# design.net
KiCad netlist of a schematic drawn in Altium Designer
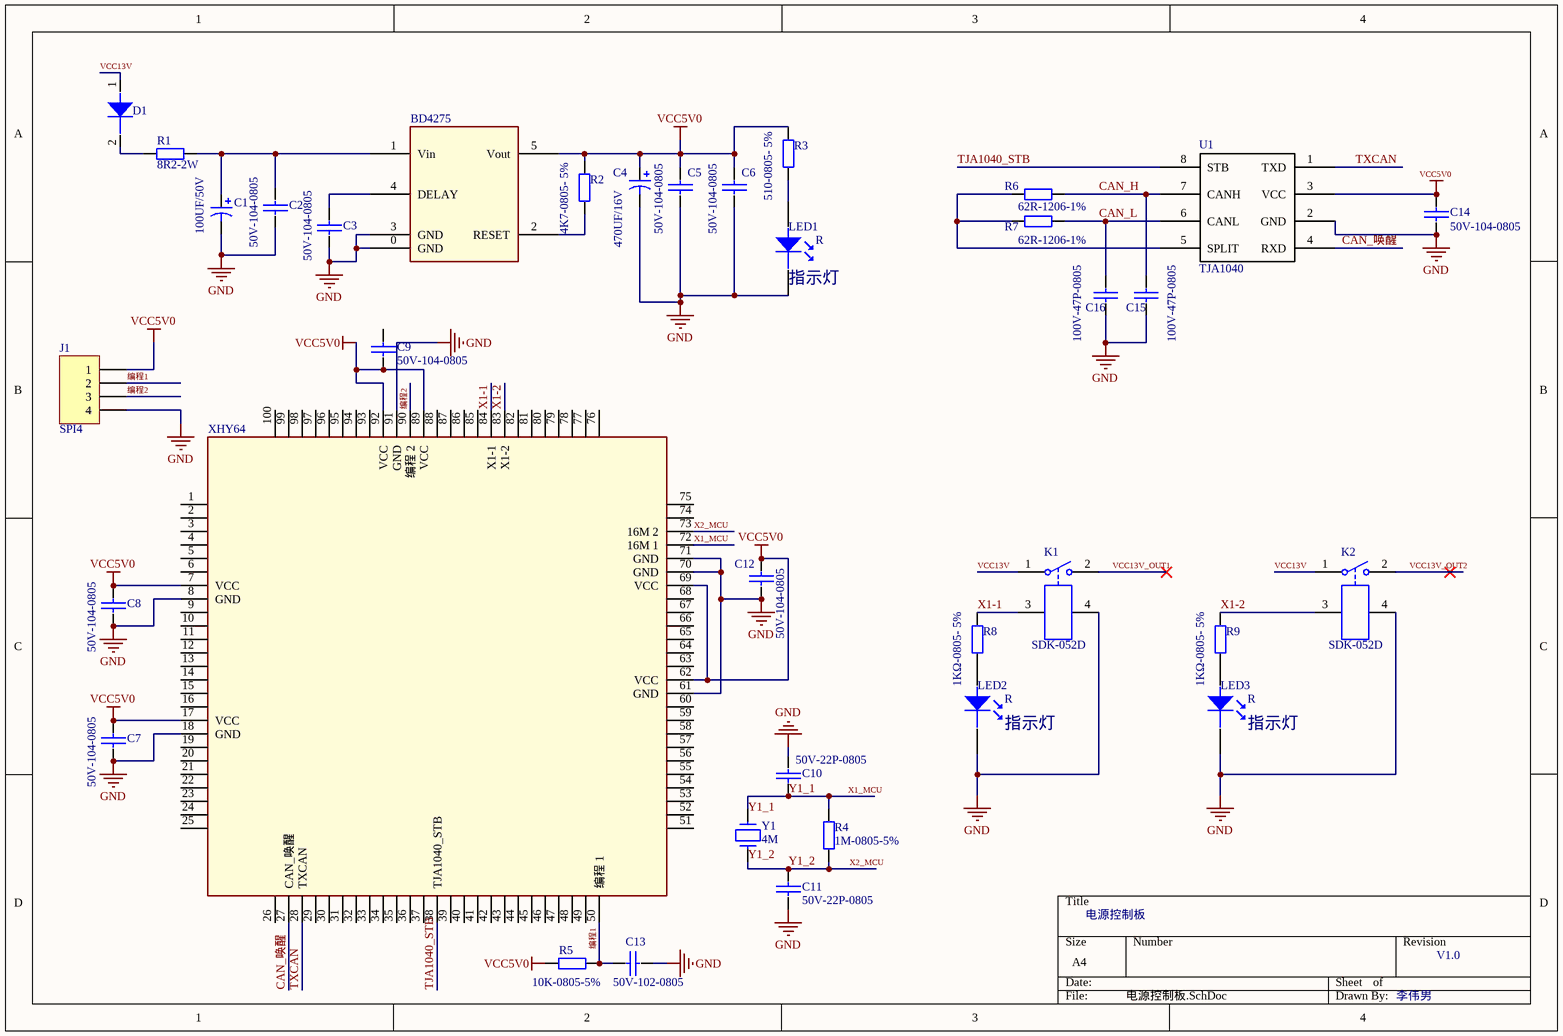
[diagram p0: 电源控制板.SchDoc]

(export (version "E")
  (design (tool "Eeschema 10.0.6"))
  (components
    (comp (ref "BD4275") (value "BD4275") (footprint "TO-263") (libsource (lib "Schlib1") (part "BD4275")))
    (comp (ref "C1")
      (value "100UF/50V")
      (footprint "RB.1/.25")
      (description "100UF      50V")
      (libsource (lib "平台图库_20170418_V1.0") (part "C470UF035S"))
    )
    (comp (ref "C2")
      (value "50V-104-0805")
      (footprint "C0805")
      (description "104     50V        10%   C0805")
      (fields (field (name "Comment") "104"))
      (libsource (lib "平台图库_20170418_V1.0") (part "C104_0805"))
    )
    (comp (ref "C3")
      (value "50V-104-0805")
      (footprint "C0805")
      (description "104     50V        10%   C0805")
      (fields (field (name "Comment") "104"))
      (libsource (lib "平台图库_20170418_V1.0") (part "C104_0805"))
    )
    (comp (ref "C4")
      (value "470UF/16V")
      (footprint "RB.1/.25")
      (description "100UF      50V      CD10X10D5")
      (libsource (lib "平台图库_20170418_V1.0") (part "C470UF016S"))
    )
    (comp (ref "C5")
      (value "50V-104-0805")
      (footprint "C0805")
      (description "104     50V        10%   C0805")
      (fields (field (name "Comment") "104"))
      (libsource (lib "平台图库_20170418_V1.0") (part "C104_0805"))
    )
    (comp (ref "C6")
      (value "50V-104-0805")
      (footprint "C0805")
      (description "104     50V        10%   C0805")
      (fields (field (name "Comment") "104"))
      (libsource (lib "平台图库_20170418_V1.0") (part "C104_0805"))
    )
    (comp (ref "C7")
      (value "50V-104-0805")
      (footprint "C0805")
      (description "104     50V        10%   C0805")
      (fields (field (name "Comment") "104"))
      (libsource (lib "平台图库_20170418_V1.0") (part "C104_0805"))
    )
    (comp (ref "C8")
      (value "50V-104-0805")
      (footprint "C0805")
      (description "104     50V        10%   C0805")
      (fields (field (name "Comment") "104"))
      (libsource (lib "平台图库_20170418_V1.0") (part "C104_0805"))
    )
    (comp (ref "C9")
      (value "50V-104-0805")
      (footprint "C0805")
      (description "104     50V        10%   C0805")
      (fields (field (name "Comment") "104"))
      (libsource (lib "平台图库_20170418_V1.0") (part "C104_0805"))
    )
    (comp (ref "C10")
      (value "50V-22P-0805")
      (footprint "C0805")
      (description "22P     50V        10%   C0805")
      (fields (field (name "Comment") "22P"))
      (libsource (lib "平台图库_20170418_V1.0") (part "C22P_0805"))
    )
    (comp (ref "C11")
      (value "50V-22P-0805")
      (footprint "C0805")
      (description "22P     50V        10%   C0805")
      (fields (field (name "Comment") "22P"))
      (libsource (lib "平台图库_20170418_V1.0") (part "C22P_0805"))
    )
    (comp (ref "C12")
      (value "50V-104-0805")
      (footprint "C0805")
      (description "104     50V        10%   C0805")
      (fields (field (name "Comment") "104"))
      (libsource (lib "平台图库_20170418_V1.0") (part "C104_0805"))
    )
    (comp (ref "C13")
      (value "50V-102-0805")
      (footprint "C0805")
      (description "104     50V        10%   C0805")
      (fields (field (name "Comment") "104"))
      (libsource (lib "平台图库_20170418_V1.0") (part "C102_0805"))
    )
    (comp (ref "C14")
      (value "50V-104-0805")
      (footprint "C0805")
      (description "104     50V        10%   C0805")
      (fields (field (name "Comment") "104"))
      (libsource (lib "平台图库_20170418_V1.0") (part "C104_0805"))
    )
    (comp (ref "C15")
      (value "100V-47P-0805")
      (footprint "C0805")
      (description "47P    100V        10%   C0805")
      (fields (field (name "Comment") "47P-100V"))
      (libsource (lib "平台图库_20170418_V1.0") (part "C47P_100V_0805"))
    )
    (comp (ref "C16")
      (value "100V-47P-0805")
      (footprint "C0805")
      (description "47P    100V        10%   C0805")
      (fields (field (name "Comment") "47P-100V"))
      (libsource (lib "平台图库_20170418_V1.0") (part "C47P_100V_0805"))
    )
    (comp (ref "D1") (value "M7") (footprint "M7-A") (libsource (lib "平台图库_20170418_V1.0") (part "TVS")))
    (comp (ref "J1")
      (value "SPI4")
      (footprint "HDR1X4")
      (description "单排针，Header, 4-Pin")
      (fields (field (name "PUBLISHER") "Altium Limited"))
      (libsource (lib "TYW_Discrete") (part "Header 4"))
    )
    (comp (ref "K1")
      (value "SDK-052D")
      (footprint "SDK-052D")
      (fields (field (name "PUBLISHER") "Altium Limited"))
      (libsource (lib "Miscellaneous Devices") (part "Relay-SPST"))
    )
    (comp (ref "K2")
      (value "SDK-052D")
      (footprint "SDK-052D")
      (fields (field (name "PUBLISHER") "Altium Limited"))
      (libsource (lib "Miscellaneous Devices") (part "Relay-SPST"))
    )
    (comp (ref "LED1")
      (value "R")
      (footprint "1206-2")
      (description "LED_R")
      (libsource (lib "平台图库_20170418_V1.0") (part "LED_R"))
    )
    (comp (ref "LED2")
      (value "R")
      (footprint "1206-2")
      (description "LED_R")
      (libsource (lib "平台图库_20170418_V1.0") (part "LED_R"))
    )
    (comp (ref "LED3")
      (value "R")
      (footprint "1206-2")
      (description "LED_R")
      (libsource (lib "平台图库_20170418_V1.0") (part "LED_R"))
    )
    (comp (ref "R1")
      (value "8R2-2W")
      (footprint "2WR")
      (description "8R2                                2W")
      (libsource (lib "平台图库_20170418_V1.0") (part "R8R22W"))
    )
    (comp (ref "R2")
      (value "4K7-0805- 5%")
      (footprint "0805")
      (description "4K7     1/8W    5%   R0805")
      (fields (field (name "Comment") "4K7"))
      (libsource (lib "平台图库_20170418_V1.0") (part "R4K7_0805_5%"))
    )
    (comp (ref "R3")
      (value "510-0805- 5%")
      (footprint "0805_2")
      (description "510Ω    5%   R0805")
      (fields (field (name "Comment") "510Ω"))
      (libsource (lib "Miscellaneous Connectors") (part "R4K7_0805_5%"))
    )
    (comp (ref "R4")
      (value "1M-0805-5%")
      (footprint "0805")
      (description "1M    1/8W    5%   R0805")
      (fields (field (name "Comment") "1M"))
      (libsource (lib "平台图库_20170418_V1.0") (part "R1M_0805_5%"))
    )
    (comp (ref "R5")
      (value "10K-0805-5%")
      (footprint "0805")
      (description "10K     1/8W    5%   R0805")
      (fields (field (name "Comment") "10K"))
      (libsource (lib "平台图库_20170418_V1.0") (part "R10K_0805_5%"))
    )
    (comp (ref "R6")
      (value "62R-1206-1%")
      (footprint "1206")
      (description "62R    1/4W     1%   R1206")
      (fields (field (name "Comment") "62R-J"))
      (libsource (lib "平台图库_20170418_V1.0") (part "R62R_1206_1%"))
    )
    (comp (ref "R7")
      (value "62R-1206-1%")
      (footprint "1206")
      (description "62R    1/4W     1%   R1206")
      (fields (field (name "Comment") "62R-J"))
      (libsource (lib "平台图库_20170418_V1.0") (part "R62R_1206_1%"))
    )
    (comp (ref "R8")
      (value "1KΩ-0805- 5%")
      (footprint "0805_2")
      (description "1KΩ    5%   R0805")
      (fields (field (name "Comment") "1KΩ"))
      (libsource (lib "Miscellaneous Connectors") (part "R4K7_0805_5%"))
    )
    (comp (ref "R9")
      (value "1KΩ-0805- 5%")
      (footprint "0805_2")
      (description "1KΩ    5%   R0805")
      (fields (field (name "Comment") "1KΩ"))
      (libsource (lib "Miscellaneous Connectors") (part "R4K7_0805_5%"))
    )
    (comp (ref "U1")
      (value "TJA1040")
      (footprint "SO-8")
      (description "CAN驱动芯片")
      (libsource (lib "平台图库_20170418_V1.0") (part "TJA1042"))
    )
    (comp (ref "XHY64") (value "XHY64") (footprint "QUAD100") (libsource (lib "Schlib1") (part "XHY64")))
    (comp (ref "Y1")
      (value "4M")
      (footprint "16M")
      (description "晶体，4M")
      (libsource (lib "TYW_Discrete") (part "XTAL"))
    )
  )
  (nets
    (net (code "1") (name "/CAN_H") (class "Default")
      (node (ref "C15") (pin "2") (pinfunction "2_2") (pintype "passive"))
      (node (ref "R6") (pin "2") (pinfunction "2_2") (pintype "passive"))
      (node (ref "U1") (pin "7") (pinfunction "CANH_7") (pintype "passive"))
    )
    (net (code "2") (name "/CAN_L") (class "Default")
      (node (ref "C16") (pin "2") (pinfunction "2_2") (pintype "passive"))
      (node (ref "R7") (pin "2") (pinfunction "2_2") (pintype "passive"))
      (node (ref "U1") (pin "6") (pinfunction "CANL_6") (pintype "passive"))
    )
    (net (code "3") (name "/CAN_唤醒") (class "Default")
      (node (ref "U1") (pin "4") (pinfunction "RXD_4") (pintype "passive"))
      (node (ref "XHY64") (pin "27") (pinfunction "CAN_唤醒_27") (pintype "passive"))
    )
    (net (code "4") (name "/TJA1040_STB") (class "Default")
      (node (ref "U1") (pin "8") (pinfunction "STB_8") (pintype "passive"))
      (node (ref "XHY64") (pin "38") (pinfunction "TJA1040_STB_38") (pintype "passive"))
    )
    (net (code "5") (name "/TXCAN") (class "Default")
      (node (ref "U1") (pin "1") (pinfunction "TXD_1") (pintype "passive"))
      (node (ref "XHY64") (pin "28") (pinfunction "TXCAN_28") (pintype "passive"))
    )
    (net (code "6") (name "/VCC13V") (class "Default")
      (node (ref "D1") (pin "1") (pinfunction "1_1") (pintype "passive"))
      (node (ref "K1") (pin "1") (pinfunction "1_1") (pintype "passive"))
      (node (ref "K2") (pin "1") (pinfunction "1_1") (pintype "passive"))
    )
    (net (code "7") (name "/VCC13V_OUT1") (class "Default")
      (node (ref "K1") (pin "2") (pinfunction "2_2") (pintype "passive+no_connect"))
    )
    (net (code "8") (name "/VCC13V_OUT2") (class "Default")
      (node (ref "K2") (pin "2") (pinfunction "2_2") (pintype "passive"))
    )
    (net (code "9") (name "/X1-1") (class "Default")
      (node (ref "K1") (pin "3") (pinfunction "3_3") (pintype "passive"))
      (node (ref "R8") (pin "2") (pinfunction "2_2") (pintype "passive"))
      (node (ref "XHY64") (pin "84") (pinfunction "X1-1_84") (pintype "passive"))
    )
    (net (code "10") (name "/X1-2") (class "Default")
      (node (ref "K2") (pin "3") (pinfunction "3_3") (pintype "passive"))
      (node (ref "R9") (pin "2") (pinfunction "2_2") (pintype "passive"))
      (node (ref "XHY64") (pin "83") (pinfunction "X1-2_83") (pintype "passive"))
    )
    (net (code "11") (name "/X1_MCU") (class "Default")
      (node (ref "C10") (pin "2") (pinfunction "2_2") (pintype "passive"))
      (node (ref "R4") (pin "2") (pinfunction "2_2") (pintype "passive"))
      (node (ref "XHY64") (pin "72") (pinfunction "16M_1_72") (pintype "passive"))
      (node (ref "Y1") (pin "2") (pinfunction "2_2") (pintype "passive"))
    )
    (net (code "12") (name "/X2_MCU") (class "Default")
      (node (ref "C11") (pin "1") (pinfunction "1_1") (pintype "passive"))
      (node (ref "R4") (pin "1") (pinfunction "1_1") (pintype "passive"))
      (node (ref "XHY64") (pin "73") (pinfunction "16M_2_73") (pintype "passive"))
      (node (ref "Y1") (pin "1") (pinfunction "1_1") (pintype "passive"))
    )
    (net (code "13") (name "/编程1") (class "Default")
      (node (ref "C13") (pin "2") (pinfunction "2_2") (pintype "passive"))
      (node (ref "J1") (pin "2") (pinfunction "2_2") (pintype "passive"))
      (node (ref "R5") (pin "1") (pinfunction "1_1") (pintype "passive"))
      (node (ref "XHY64") (pin "50") (pinfunction "编程_1_50") (pintype "passive"))
    )
    (net (code "14") (name "/编程2") (class "Default")
      (node (ref "J1") (pin "3") (pinfunction "3_3") (pintype "passive"))
      (node (ref "XHY64") (pin "90") (pinfunction "编程_2_90") (pintype "passive"))
    )
    (net (code "15") (name "GND") (class "Default")
      (node (ref "BD4275") (pin "0") (pinfunction "GND_0") (pintype "passive"))
      (node (ref "BD4275") (pin "3") (pinfunction "GND_3") (pintype "passive"))
      (node (ref "C1") (pin "2") (pinfunction "2_2") (pintype "passive"))
      (node (ref "C10") (pin "1") (pinfunction "1_1") (pintype "passive"))
      (node (ref "C11") (pin "2") (pinfunction "2_2") (pintype "passive"))
      (node (ref "C12") (pin "2") (pinfunction "2_2") (pintype "passive"))
      (node (ref "C13") (pin "1") (pinfunction "1_1") (pintype "passive"))
      (node (ref "C14") (pin "1") (pinfunction "1_1") (pintype "passive"))
      (node (ref "C15") (pin "1") (pinfunction "1_1") (pintype "passive"))
      (node (ref "C16") (pin "1") (pinfunction "1_1") (pintype "passive"))
      (node (ref "C2") (pin "1") (pinfunction "1_1") (pintype "passive"))
      (node (ref "C3") (pin "1") (pinfunction "1_1") (pintype "passive"))
      (node (ref "C4") (pin "2") (pinfunction "2_2") (pintype "passive"))
      (node (ref "C5") (pin "1") (pinfunction "1_1") (pintype "passive"))
      (node (ref "C6") (pin "1") (pinfunction "1_1") (pintype "passive"))
      (node (ref "C7") (pin "2") (pinfunction "2_2") (pintype "passive"))
      (node (ref "C8") (pin "2") (pinfunction "2_2") (pintype "passive"))
      (node (ref "J1") (pin "4") (pinfunction "4_4") (pintype "passive"))
      (node (ref "K1") (pin "4") (pinfunction "4_4") (pintype "passive"))
      (node (ref "K2") (pin "4") (pinfunction "4_4") (pintype "passive"))
      (node (ref "LED1") (pin "2") (pinfunction "2_2") (pintype "passive"))
      (node (ref "LED2") (pin "2") (pinfunction "2_2") (pintype "passive"))
      (node (ref "LED3") (pin "2") (pinfunction "2_2") (pintype "passive"))
      (node (ref "U1") (pin "2") (pinfunction "GND_2") (pintype "passive"))
      (node (ref "XHY64") (pin "18") (pinfunction "GND_18") (pintype "passive"))
      (node (ref "XHY64") (pin "61") (pinfunction "GND_61") (pintype "passive"))
      (node (ref "XHY64") (pin "70") (pinfunction "GND_70") (pintype "passive"))
      (node (ref "XHY64") (pin "71") (pinfunction "GND_71") (pintype "passive"))
      (node (ref "XHY64") (pin "8") (pinfunction "GND_8") (pintype "passive"))
      (node (ref "XHY64") (pin "91") (pinfunction "GND_91") (pintype "passive"))
    )
    (net (code "16") (name "Net-(BD4275-DELAY)") (class "Default")
      (node (ref "BD4275") (pin "4") (pinfunction "DELAY_4") (pintype "passive"))
      (node (ref "C3") (pin "2") (pinfunction "2_2") (pintype "passive"))
    )
    (net (code "17") (name "Net-(BD4275-RESET)") (class "Default")
      (node (ref "BD4275") (pin "2") (pinfunction "RESET_2") (pintype "passive"))
      (node (ref "R2") (pin "1") (pinfunction "1_1") (pintype "passive"))
    )
    (net (code "18") (name "Net-(BD4275-Vin)") (class "Default")
      (node (ref "BD4275") (pin "1") (pinfunction "Vin_1") (pintype "passive"))
      (node (ref "C1") (pin "1") (pinfunction "1_1") (pintype "passive"))
      (node (ref "C2") (pin "2") (pinfunction "2_2") (pintype "passive"))
      (node (ref "R1") (pin "2") (pinfunction "2_2") (pintype "passive"))
    )
    (net (code "19") (name "Net-(D1-Pad2)") (class "Default")
      (node (ref "D1") (pin "2") (pinfunction "2_2") (pintype "passive"))
      (node (ref "R1") (pin "1") (pinfunction "1_1") (pintype "passive"))
    )
    (net (code "20") (name "Net-(LED1-Pad1)") (class "Default")
      (node (ref "LED1") (pin "1") (pinfunction "1_1") (pintype "passive"))
      (node (ref "R3") (pin "1") (pinfunction "1_1") (pintype "passive"))
    )
    (net (code "21") (name "Net-(U1-SPLIT)") (class "Default")
      (node (ref "R6") (pin "1") (pinfunction "1_1") (pintype "passive"))
      (node (ref "R7") (pin "1") (pinfunction "1_1") (pintype "passive"))
      (node (ref "U1") (pin "5") (pinfunction "SPLIT_5") (pintype "passive"))
    )
    (net (code "22") (name "VCC5V0") (class "Default")
      (node (ref "BD4275") (pin "5") (pinfunction "Vout_5") (pintype "passive"))
      (node (ref "C12") (pin "1") (pinfunction "1_1") (pintype "passive"))
      (node (ref "C14") (pin "2") (pinfunction "2_2") (pintype "passive"))
      (node (ref "C4") (pin "1") (pinfunction "1_1") (pintype "passive"))
      (node (ref "C5") (pin "2") (pinfunction "2_2") (pintype "passive"))
      (node (ref "C6") (pin "2") (pinfunction "2_2") (pintype "passive"))
      (node (ref "C7") (pin "1") (pinfunction "1_1") (pintype "passive"))
      (node (ref "C8") (pin "1") (pinfunction "1_1") (pintype "passive"))
      (node (ref "C9") (pin "2") (pinfunction "2_2") (pintype "passive"))
      (node (ref "J1") (pin "1") (pinfunction "1_1") (pintype "passive"))
      (node (ref "R2") (pin "2") (pinfunction "2_2") (pintype "passive"))
      (node (ref "R3") (pin "2") (pinfunction "2_2") (pintype "passive"))
      (node (ref "R5") (pin "2") (pinfunction "2_2") (pintype "passive"))
      (node (ref "U1") (pin "3") (pinfunction "VCC_3") (pintype "passive"))
      (node (ref "XHY64") (pin "17") (pinfunction "VCC_17") (pintype "passive"))
      (node (ref "XHY64") (pin "62") (pinfunction "VCC_62") (pintype "passive"))
      (node (ref "XHY64") (pin "69") (pinfunction "VCC_69") (pintype "passive"))
      (node (ref "XHY64") (pin "7") (pinfunction "VCC_7") (pintype "passive"))
      (node (ref "XHY64") (pin "89") (pinfunction "VCC_89") (pintype "passive"))
      (node (ref "XHY64") (pin "92") (pinfunction "VCC_92") (pintype "passive"))
    )
    (net (code "23") (name "unconnected-(C9-Pad1)") (class "Default")
      (node (ref "C9") (pin "1") (pinfunction "1_1") (pintype "passive"))
    )
    (net (code "24") (name "unconnected-(LED2-Pad1)") (class "Default")
      (node (ref "LED2") (pin "1") (pinfunction "1_1") (pintype "passive"))
    )
    (net (code "25") (name "unconnected-(LED3-Pad1)") (class "Default")
      (node (ref "LED3") (pin "1") (pinfunction "1_1") (pintype "passive"))
    )
    (net (code "26") (name "unconnected-(R8-Pad1)") (class "Default")
      (node (ref "R8") (pin "1") (pinfunction "1_1") (pintype "passive"))
    )
    (net (code "27") (name "unconnected-(R9-Pad1)") (class "Default")
      (node (ref "R9") (pin "1") (pinfunction "1_1") (pintype "passive"))
    )
    (net (code "28") (name "unconnected-(XHY64-Pad1)") (class "Default")
      (node (ref "XHY64") (pin "1") (pintype "passive"))
    )
    (net (code "29") (name "unconnected-(XHY64-Pad2)") (class "Default")
      (node (ref "XHY64") (pin "2") (pintype "passive"))
    )
    (net (code "30") (name "unconnected-(XHY64-Pad3)") (class "Default")
      (node (ref "XHY64") (pin "3") (pintype "passive"))
    )
    (net (code "31") (name "unconnected-(XHY64-Pad4)") (class "Default")
      (node (ref "XHY64") (pin "4") (pintype "passive"))
    )
    (net (code "32") (name "unconnected-(XHY64-Pad5)") (class "Default")
      (node (ref "XHY64") (pin "5") (pintype "passive"))
    )
    (net (code "33") (name "unconnected-(XHY64-Pad6)") (class "Default")
      (node (ref "XHY64") (pin "6") (pintype "passive"))
    )
    (net (code "34") (name "unconnected-(XHY64-Pad9)") (class "Default")
      (node (ref "XHY64") (pin "9") (pintype "passive"))
    )
    (net (code "35") (name "unconnected-(XHY64-Pad10)") (class "Default")
      (node (ref "XHY64") (pin "10") (pintype "passive"))
    )
    (net (code "36") (name "unconnected-(XHY64-Pad11)") (class "Default")
      (node (ref "XHY64") (pin "11") (pintype "passive"))
    )
    (net (code "37") (name "unconnected-(XHY64-Pad12)") (class "Default")
      (node (ref "XHY64") (pin "12") (pintype "passive"))
    )
    (net (code "38") (name "unconnected-(XHY64-Pad13)") (class "Default")
      (node (ref "XHY64") (pin "13") (pintype "passive"))
    )
    (net (code "39") (name "unconnected-(XHY64-Pad14)") (class "Default")
      (node (ref "XHY64") (pin "14") (pintype "passive"))
    )
    (net (code "40") (name "unconnected-(XHY64-Pad15)") (class "Default")
      (node (ref "XHY64") (pin "15") (pintype "passive"))
    )
    (net (code "41") (name "unconnected-(XHY64-Pad16)") (class "Default")
      (node (ref "XHY64") (pin "16") (pintype "passive"))
    )
    (net (code "42") (name "unconnected-(XHY64-Pad19)") (class "Default")
      (node (ref "XHY64") (pin "19") (pintype "passive"))
    )
    (net (code "43") (name "unconnected-(XHY64-Pad20)") (class "Default")
      (node (ref "XHY64") (pin "20") (pintype "passive"))
    )
    (net (code "44") (name "unconnected-(XHY64-Pad21)") (class "Default")
      (node (ref "XHY64") (pin "21") (pintype "passive"))
    )
    (net (code "45") (name "unconnected-(XHY64-Pad22)") (class "Default")
      (node (ref "XHY64") (pin "22") (pintype "passive"))
    )
    (net (code "46") (name "unconnected-(XHY64-Pad23)") (class "Default")
      (node (ref "XHY64") (pin "23") (pintype "passive"))
    )
    (net (code "47") (name "unconnected-(XHY64-Pad24)") (class "Default")
      (node (ref "XHY64") (pin "24") (pintype "passive"))
    )
    (net (code "48") (name "unconnected-(XHY64-Pad25)") (class "Default")
      (node (ref "XHY64") (pin "25") (pintype "passive"))
    )
    (net (code "49") (name "unconnected-(XHY64-Pad26)") (class "Default")
      (node (ref "XHY64") (pin "26") (pintype "passive"))
    )
    (net (code "50") (name "unconnected-(XHY64-Pad29)") (class "Default")
      (node (ref "XHY64") (pin "29") (pintype "passive"))
    )
    (net (code "51") (name "unconnected-(XHY64-Pad30)") (class "Default")
      (node (ref "XHY64") (pin "30") (pintype "passive"))
    )
    (net (code "52") (name "unconnected-(XHY64-Pad31)") (class "Default")
      (node (ref "XHY64") (pin "31") (pintype "passive"))
    )
    (net (code "53") (name "unconnected-(XHY64-Pad32)") (class "Default")
      (node (ref "XHY64") (pin "32") (pintype "passive"))
    )
    (net (code "54") (name "unconnected-(XHY64-Pad33)") (class "Default")
      (node (ref "XHY64") (pin "33") (pintype "passive"))
    )
    (net (code "55") (name "unconnected-(XHY64-Pad34)") (class "Default")
      (node (ref "XHY64") (pin "34") (pintype "passive"))
    )
    (net (code "56") (name "unconnected-(XHY64-Pad35)") (class "Default")
      (node (ref "XHY64") (pin "35") (pintype "passive"))
    )
    (net (code "57") (name "unconnected-(XHY64-Pad36)") (class "Default")
      (node (ref "XHY64") (pin "36") (pintype "passive"))
    )
    (net (code "58") (name "unconnected-(XHY64-Pad37)") (class "Default")
      (node (ref "XHY64") (pin "37") (pintype "passive"))
    )
    (net (code "59") (name "unconnected-(XHY64-Pad39)") (class "Default")
      (node (ref "XHY64") (pin "39") (pintype "passive"))
    )
    (net (code "60") (name "unconnected-(XHY64-Pad40)") (class "Default")
      (node (ref "XHY64") (pin "40") (pintype "passive"))
    )
    (net (code "61") (name "unconnected-(XHY64-Pad41)") (class "Default")
      (node (ref "XHY64") (pin "41") (pintype "passive"))
    )
    (net (code "62") (name "unconnected-(XHY64-Pad42)") (class "Default")
      (node (ref "XHY64") (pin "42") (pintype "passive"))
    )
    (net (code "63") (name "unconnected-(XHY64-Pad43)") (class "Default")
      (node (ref "XHY64") (pin "43") (pintype "passive"))
    )
    (net (code "64") (name "unconnected-(XHY64-Pad44)") (class "Default")
      (node (ref "XHY64") (pin "44") (pintype "passive"))
    )
    (net (code "65") (name "unconnected-(XHY64-Pad45)") (class "Default")
      (node (ref "XHY64") (pin "45") (pintype "passive"))
    )
    (net (code "66") (name "unconnected-(XHY64-Pad46)") (class "Default")
      (node (ref "XHY64") (pin "46") (pintype "passive"))
    )
    (net (code "67") (name "unconnected-(XHY64-Pad47)") (class "Default")
      (node (ref "XHY64") (pin "47") (pintype "passive"))
    )
    (net (code "68") (name "unconnected-(XHY64-Pad48)") (class "Default")
      (node (ref "XHY64") (pin "48") (pintype "passive"))
    )
    (net (code "69") (name "unconnected-(XHY64-Pad49)") (class "Default")
      (node (ref "XHY64") (pin "49") (pintype "passive"))
    )
    (net (code "70") (name "unconnected-(XHY64-Pad51)") (class "Default")
      (node (ref "XHY64") (pin "51") (pintype "passive"))
    )
    (net (code "71") (name "unconnected-(XHY64-Pad52)") (class "Default")
      (node (ref "XHY64") (pin "52") (pintype "passive"))
    )
    (net (code "72") (name "unconnected-(XHY64-Pad53)") (class "Default")
      (node (ref "XHY64") (pin "53") (pintype "passive"))
    )
    (net (code "73") (name "unconnected-(XHY64-Pad54)") (class "Default")
      (node (ref "XHY64") (pin "54") (pintype "passive"))
    )
    (net (code "74") (name "unconnected-(XHY64-Pad55)") (class "Default")
      (node (ref "XHY64") (pin "55") (pintype "passive"))
    )
    (net (code "75") (name "unconnected-(XHY64-Pad56)") (class "Default")
      (node (ref "XHY64") (pin "56") (pintype "passive"))
    )
    (net (code "76") (name "unconnected-(XHY64-Pad57)") (class "Default")
      (node (ref "XHY64") (pin "57") (pintype "passive"))
    )
    (net (code "77") (name "unconnected-(XHY64-Pad58)") (class "Default")
      (node (ref "XHY64") (pin "58") (pintype "passive"))
    )
    (net (code "78") (name "unconnected-(XHY64-Pad59)") (class "Default")
      (node (ref "XHY64") (pin "59") (pintype "passive"))
    )
    (net (code "79") (name "unconnected-(XHY64-Pad60)") (class "Default")
      (node (ref "XHY64") (pin "60") (pintype "passive"))
    )
    (net (code "80") (name "unconnected-(XHY64-Pad63)") (class "Default")
      (node (ref "XHY64") (pin "63") (pintype "passive"))
    )
    (net (code "81") (name "unconnected-(XHY64-Pad64)") (class "Default")
      (node (ref "XHY64") (pin "64") (pintype "passive"))
    )
    (net (code "82") (name "unconnected-(XHY64-Pad65)") (class "Default")
      (node (ref "XHY64") (pin "65") (pintype "passive"))
    )
    (net (code "83") (name "unconnected-(XHY64-Pad66)") (class "Default")
      (node (ref "XHY64") (pin "66") (pintype "passive"))
    )
    (net (code "84") (name "unconnected-(XHY64-Pad67)") (class "Default")
      (node (ref "XHY64") (pin "67") (pintype "passive"))
    )
    (net (code "85") (name "unconnected-(XHY64-Pad68)") (class "Default")
      (node (ref "XHY64") (pin "68") (pintype "passive"))
    )
    (net (code "86") (name "unconnected-(XHY64-Pad74)") (class "Default")
      (node (ref "XHY64") (pin "74") (pintype "passive"))
    )
    (net (code "87") (name "unconnected-(XHY64-Pad75)") (class "Default")
      (node (ref "XHY64") (pin "75") (pintype "passive"))
    )
    (net (code "88") (name "unconnected-(XHY64-Pad76)") (class "Default")
      (node (ref "XHY64") (pin "76") (pintype "passive"))
    )
    (net (code "89") (name "unconnected-(XHY64-Pad77)") (class "Default")
      (node (ref "XHY64") (pin "77") (pintype "passive"))
    )
    (net (code "90") (name "unconnected-(XHY64-Pad78)") (class "Default")
      (node (ref "XHY64") (pin "78") (pintype "passive"))
    )
    (net (code "91") (name "unconnected-(XHY64-Pad79)") (class "Default")
      (node (ref "XHY64") (pin "79") (pintype "passive"))
    )
    (net (code "92") (name "unconnected-(XHY64-Pad80)") (class "Default")
      (node (ref "XHY64") (pin "80") (pintype "passive"))
    )
    (net (code "93") (name "unconnected-(XHY64-Pad81)") (class "Default")
      (node (ref "XHY64") (pin "81") (pintype "passive"))
    )
    (net (code "94") (name "unconnected-(XHY64-Pad82)") (class "Default")
      (node (ref "XHY64") (pin "82") (pintype "passive"))
    )
    (net (code "95") (name "unconnected-(XHY64-Pad85)") (class "Default")
      (node (ref "XHY64") (pin "85") (pintype "passive"))
    )
    (net (code "96") (name "unconnected-(XHY64-Pad86)") (class "Default")
      (node (ref "XHY64") (pin "86") (pintype "passive"))
    )
    (net (code "97") (name "unconnected-(XHY64-Pad87)") (class "Default")
      (node (ref "XHY64") (pin "87") (pintype "passive"))
    )
    (net (code "98") (name "unconnected-(XHY64-Pad88)") (class "Default")
      (node (ref "XHY64") (pin "88") (pintype "passive"))
    )
    (net (code "99") (name "unconnected-(XHY64-Pad93)") (class "Default")
      (node (ref "XHY64") (pin "93") (pintype "passive"))
    )
    (net (code "100") (name "unconnected-(XHY64-Pad94)") (class "Default")
      (node (ref "XHY64") (pin "94") (pintype "passive"))
    )
    (net (code "101") (name "unconnected-(XHY64-Pad95)") (class "Default")
      (node (ref "XHY64") (pin "95") (pintype "passive"))
    )
    (net (code "102") (name "unconnected-(XHY64-Pad96)") (class "Default")
      (node (ref "XHY64") (pin "96") (pintype "passive"))
    )
    (net (code "103") (name "unconnected-(XHY64-Pad97)") (class "Default")
      (node (ref "XHY64") (pin "97") (pintype "passive"))
    )
    (net (code "104") (name "unconnected-(XHY64-Pad98)") (class "Default")
      (node (ref "XHY64") (pin "98") (pintype "passive"))
    )
    (net (code "105") (name "unconnected-(XHY64-Pad99)") (class "Default")
      (node (ref "XHY64") (pin "99") (pintype "passive"))
    )
    (net (code "106") (name "unconnected-(XHY64-Pad100)") (class "Default")
      (node (ref "XHY64") (pin "100") (pintype "passive"))
    )
  )
)
